# powerbrain2.net
KiCad netlist of a schematic drawn in EAGLE
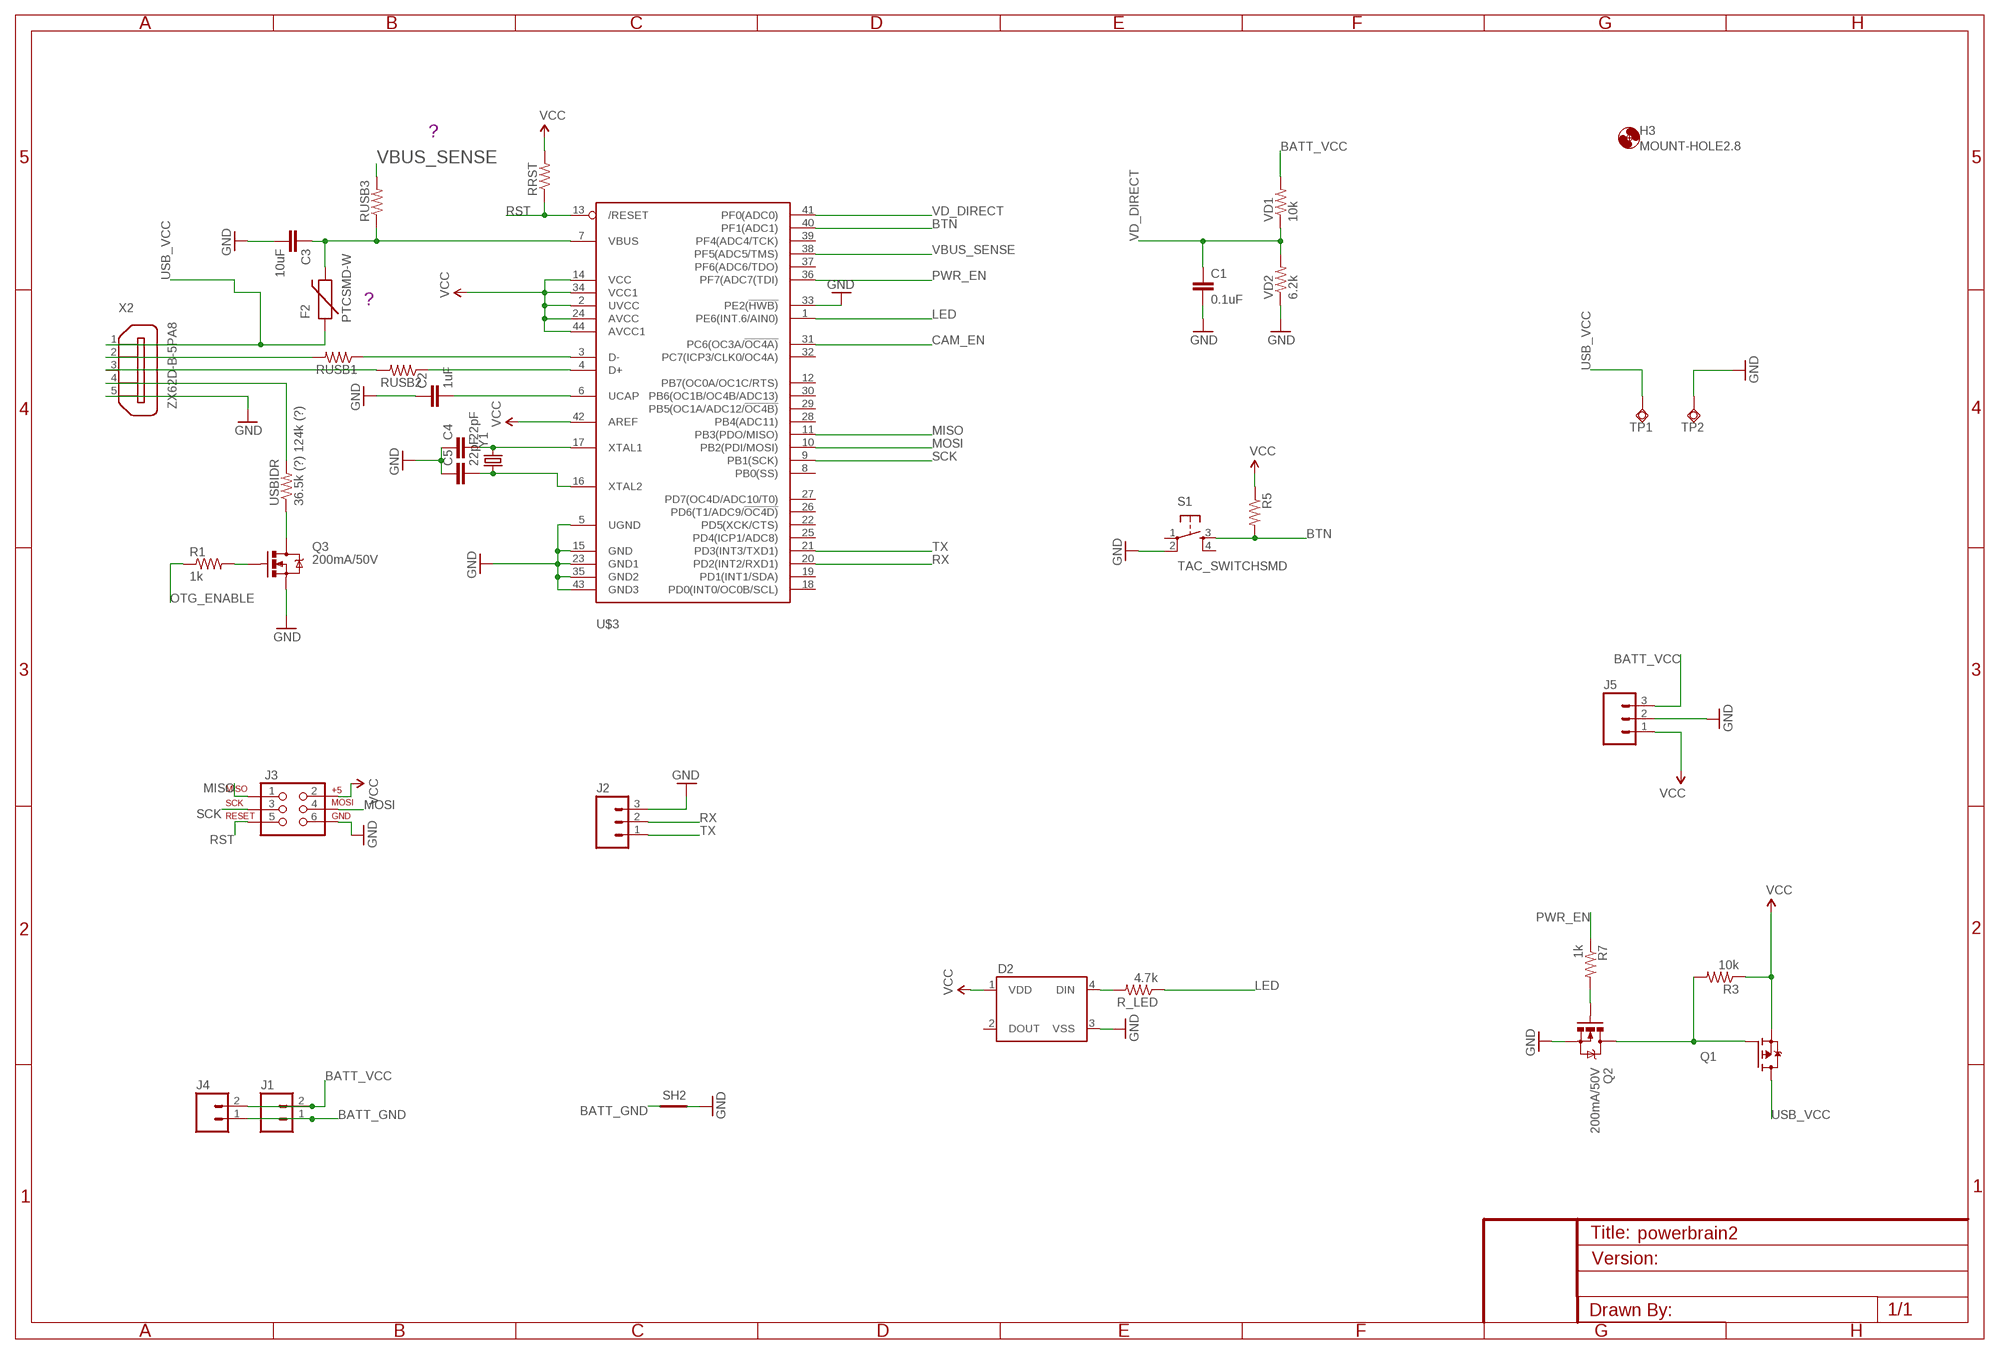
[diagram p0: schematic, sheet 1]

(export (version "E")
  (design (tool "Eeschema 10.0.6"))
  (components
    (comp (ref "C1")
      (value "0.1uF")
      (footprint "eagle-import:1206")
      (libsource (lib "eagle-import") (part "SparkFun-Passives_CAP1206"))
    )
    (comp (ref "C2")
      (value "1uF")
      (footprint "eagle-import:1206")
      (libsource (lib "eagle-import") (part "CAP1206"))
    )
    (comp (ref "C3")
      (value "10uF")
      (footprint "eagle-import:1206")
      (libsource (lib "eagle-import") (part "SparkFun-Passives_CAP1206"))
    )
    (comp (ref "C4")
      (value "22pF")
      (footprint "eagle-import:1206")
      (libsource (lib "eagle-import") (part "SparkFun-Passives_CAP1206"))
    )
    (comp (ref "C5")
      (value "22pF")
      (footprint "eagle-import:1206")
      (libsource (lib "eagle-import") (part "SparkFun-Passives_CAP1206"))
    )
    (comp (ref "D2")
      (value "WS2812B")
      (footprint "eagle-import:WS2812B")
      (libsource (lib "eagle-import") (part "WS2812B"))
    )
    (comp (ref "F2")
      (value "PTCSMD-W")
      (footprint "eagle-import:PTC-1206-WIDE")
      (libsource (lib "eagle-import") (part "PTCSMD-W"))
    )
    (comp (ref "H3")
      (value "MOUNT-HOLE2.8")
      (footprint "eagle-import:2,8")
      (libsource (lib "eagle-import") (part "MOUNT-HOLE2.8"))
    )
    (comp (ref "J1")
      (value "M02LOCK")
      (footprint "eagle-import:1X02_LOCK")
      (libsource (lib "eagle-import") (part "M02LOCK"))
    )
    (comp (ref "J2")
      (value "M03PTH")
      (footprint "eagle-import:1X03")
      (libsource (lib "eagle-import") (part "M03PTH"))
    )
    (comp (ref "J3")
      (value "AVR_SPI_PRG_6PTH")
      (footprint "eagle-import:2X3")
      (libsource (lib "eagle-import") (part "AVR_SPI_PRG_6PTH"))
    )
    (comp (ref "J4")
      (value "M02LOCK")
      (footprint "eagle-import:1X02_LOCK")
      (libsource (lib "eagle-import") (part "M02LOCK"))
    )
    (comp (ref "J5")
      (value "M03LOCK")
      (footprint "eagle-import:1X03_LOCK")
      (libsource (lib "eagle-import") (part "M03LOCK"))
    )
    (comp (ref "Q1")
      (value "FDD4141TO252")
      (footprint "eagle-import:TO252")
      (libsource (lib "eagle-import") (part "FDD4141TO252"))
    )
    (comp (ref "Q2")
      (value "200mA/50V")
      (footprint "eagle-import:SOT23-3")
      (libsource (lib "eagle-import") (part "MOSFET-NCHANNELBSS138"))
    )
    (comp (ref "Q3")
      (value "200mA/50V")
      (footprint "eagle-import:SOT23-3")
      (libsource (lib "eagle-import") (part "MOSFET-NCHANNELBSS138"))
    )
    (comp (ref "R1")
      (value "1k")
      (footprint "eagle-import:1206")
      (libsource (lib "eagle-import") (part "SparkFun-Resistors_RESISTOR1206"))
    )
    (comp (ref "R3")
      (value "10k")
      (footprint "eagle-import:1206")
      (libsource (lib "eagle-import") (part "SparkFun-Resistors_RESISTOR1206"))
    )
    (comp (ref "R5")
      (value "RESISTOR1206")
      (footprint "eagle-import:1206")
      (libsource (lib "eagle-import") (part "RESISTOR1206"))
    )
    (comp (ref "R7")
      (value "1k")
      (footprint "eagle-import:1206")
      (libsource (lib "eagle-import") (part "SparkFun-Resistors_RESISTOR1206"))
    )
    (comp (ref "RRST")
      (value "RESISTOR1206")
      (footprint "eagle-import:1206")
      (libsource (lib "eagle-import") (part "RESISTOR1206"))
    )
    (comp (ref "RUSB1")
      (value "RESISTOR1206")
      (footprint "eagle-import:1206")
      (libsource (lib "eagle-import") (part "RESISTOR1206"))
    )
    (comp (ref "RUSB2")
      (value "RESISTOR1206")
      (footprint "eagle-import:1206")
      (libsource (lib "eagle-import") (part "RESISTOR1206"))
    )
    (comp (ref "RUSB3")
      (value "RESISTOR1206")
      (footprint "eagle-import:1206")
      (libsource (lib "eagle-import") (part "RESISTOR1206"))
    )
    (comp (ref "R_LED")
      (value "4.7k")
      (footprint "eagle-import:1206")
      (libsource (lib "eagle-import") (part "SparkFun-Resistors_RESISTOR1206"))
    )
    (comp (ref "S1")
      (value "TAC_SWITCHSMD")
      (footprint "eagle-import:TACTILE-PTH")
      (libsource (lib "eagle-import") (part "TAC_SWITCHPTH"))
    )
    (comp (ref "SH2")
      (value "SHORT-HT5")
      (footprint "eagle-import:SHORT_TOP-50")
      (libsource (lib "eagle-import") (part "SHORT-HT5"))
    )
    (comp (ref "TP1")
      (value "TPSQTP20R")
      (footprint "eagle-import:TP20R")
      (libsource (lib "eagle-import") (part "TPSQTP20R"))
    )
    (comp (ref "TP2")
      (value "TPSQTP20R")
      (footprint "eagle-import:TP20R")
      (libsource (lib "eagle-import") (part "TPSQTP20R"))
    )
    (comp (ref "U$3")
      (value "ATMEGA32U4-AU")
      (footprint "eagle-import:TQFP44")
      (libsource (lib "eagle-import") (part "ATMEGA32U4-AU"))
    )
    (comp (ref "USBIDR")
      (value "36.5k (?) 124k (?)")
      (footprint "eagle-import:1206")
      (libsource (lib "eagle-import") (part "RESISTOR1206"))
    )
    (comp (ref "VD1")
      (value "10k")
      (footprint "eagle-import:1206")
      (libsource (lib "eagle-import") (part "RESISTOR1206"))
    )
    (comp (ref "VD2")
      (value "6.2k")
      (footprint "eagle-import:1206")
      (libsource (lib "eagle-import") (part "RESISTOR1206"))
    )
    (comp (ref "X2")
      (value "ZX62D-B-5PA8")
      (footprint "eagle-import:ZX62D-B-5PA8")
      (fields (field (name "MF") "Hirose"))
      (libsource (lib "eagle-import") (part "ZX62D-B-5PA8"))
    )
    (comp (ref "Y1")
      (value "CRYSTALCRYSTAL-SMD-5X3-16MHZ")
      (footprint "eagle-import:CRYSTAL-SMD-5X3")
      (libsource (lib "eagle-import") (part "CRYSTALCRYSTAL-SMD-5X3-16MHZ"))
    )
  )
  (nets
    (net (code "1") (name "/BATT_GND") (class "Default")
      (node (ref "J1") (pin "1") (pinfunction "1_1") (pintype "passive"))
      (node (ref "J4") (pin "1") (pinfunction "1_1") (pintype "passive"))
      (node (ref "SH2") (pin "1") (pinfunction "P$1_1") (pintype "bidirectional"))
    )
    (net (code "2") (name "/BATT_VCC") (class "Default")
      (node (ref "J1") (pin "2") (pinfunction "2_2") (pintype "passive"))
      (node (ref "J4") (pin "2") (pinfunction "2_2") (pintype "passive"))
      (node (ref "J5") (pin "3") (pinfunction "3_3") (pintype "passive"))
      (node (ref "VD1") (pin "2") (pinfunction "2_2") (pintype "passive"))
    )
    (net (code "3") (name "/BTN") (class "Default")
      (node (ref "R5") (pin "2") (pinfunction "2_2") (pintype "passive"))
      (node (ref "S1") (pin "3") (pinfunction "3_3") (pintype "passive"))
      (node (ref "U$3") (pin "40") (pinfunction "PF1(ADC1)_40") (pintype "bidirectional"))
    )
    (net (code "4") (name "/CAM_EN") (class "Default")
      (node (ref "U$3") (pin "31") (pinfunction "PC6(OC3A/~{OC4A})_31") (pintype "bidirectional"))
    )
    (net (code "5") (name "/LED") (class "Default")
      (node (ref "R_LED") (pin "1") (pinfunction "1_1") (pintype "passive"))
      (node (ref "U$3") (pin "1") (pinfunction "PE6(INT.6/AIN0)_1") (pintype "bidirectional"))
    )
    (net (code "6") (name "/MISO") (class "Default")
      (node (ref "J3") (pin "1") (pinfunction "1_1") (pintype "passive"))
      (node (ref "U$3") (pin "11") (pinfunction "PB3(PDO/MISO)_11") (pintype "bidirectional"))
    )
    (net (code "7") (name "/MOSI") (class "Default")
      (node (ref "J3") (pin "4") (pinfunction "4_4") (pintype "passive"))
      (node (ref "U$3") (pin "10") (pinfunction "PB2(PDI/MOSI)_10") (pintype "bidirectional"))
    )
    (net (code "8") (name "/OTG_ENABLE") (class "Default")
      (node (ref "R1") (pin "1") (pinfunction "1_1") (pintype "passive"))
    )
    (net (code "9") (name "/PWR_EN") (class "Default")
      (node (ref "R7") (pin "1") (pinfunction "1_1") (pintype "passive"))
      (node (ref "U$3") (pin "36") (pinfunction "PF7(ADC7(TDI)_36") (pintype "bidirectional"))
    )
    (net (code "10") (name "/RST") (class "Default")
      (node (ref "J3") (pin "5") (pinfunction "5_5") (pintype "passive"))
      (node (ref "RRST") (pin "1") (pinfunction "1_1") (pintype "passive"))
      (node (ref "U$3") (pin "13") (pinfunction "/RESET_13") (pintype "bidirectional"))
    )
    (net (code "11") (name "/RX") (class "Default")
      (node (ref "J2") (pin "2") (pinfunction "2_2") (pintype "passive"))
      (node (ref "U$3") (pin "20") (pinfunction "PD2(INT2/RXD1)_20") (pintype "bidirectional"))
    )
    (net (code "12") (name "/SCK") (class "Default")
      (node (ref "J3") (pin "3") (pinfunction "3_3") (pintype "passive"))
      (node (ref "U$3") (pin "9") (pinfunction "PB1(SCK)_9") (pintype "bidirectional"))
    )
    (net (code "13") (name "/TX") (class "Default")
      (node (ref "J2") (pin "1") (pinfunction "1_1") (pintype "passive"))
      (node (ref "U$3") (pin "21") (pinfunction "PD3(INT3/TXD1)_21") (pintype "bidirectional"))
    )
    (net (code "14") (name "/USB_VCC") (class "Default")
      (node (ref "F2") (pin "1") (pinfunction "1_1") (pintype "bidirectional"))
      (node (ref "Q1") (pin "3") (pinfunction "D_3") (pintype "passive"))
      (node (ref "TP1") (pin "TP") (pinfunction "TP_TP") (pintype "input"))
      (node (ref "X2") (pin "1") (pinfunction "1_1") (pintype "passive"))
    )
    (net (code "15") (name "/VBUS_SENSE") (class "Default")
      (node (ref "RUSB3") (pin "2") (pinfunction "2_2") (pintype "passive"))
      (node (ref "U$3") (pin "38") (pinfunction "PF5(ADC5/TMS)_38") (pintype "bidirectional"))
    )
    (net (code "16") (name "/VD_DIRECT") (class "Default")
      (node (ref "C1") (pin "1") (pinfunction "1_1") (pintype "passive"))
      (node (ref "U$3") (pin "41") (pinfunction "PF0(ADC0)_41") (pintype "bidirectional"))
      (node (ref "VD1") (pin "1") (pinfunction "1_1") (pintype "passive"))
      (node (ref "VD2") (pin "2") (pinfunction "2_2") (pintype "passive"))
    )
    (net (code "17") (name "GND") (class "Default")
      (node (ref "C1") (pin "2") (pinfunction "2_2") (pintype "passive"))
      (node (ref "C2") (pin "1") (pinfunction "1_1") (pintype "passive"))
      (node (ref "C3") (pin "2") (pinfunction "2_2") (pintype "passive"))
      (node (ref "C4") (pin "1") (pinfunction "1_1") (pintype "passive"))
      (node (ref "C5") (pin "1") (pinfunction "1_1") (pintype "passive"))
      (node (ref "D2") (pin "3") (pinfunction "VSS_3") (pintype "power_in"))
      (node (ref "J2") (pin "3") (pinfunction "3_3") (pintype "passive"))
      (node (ref "J3") (pin "6") (pinfunction "6_6") (pintype "passive"))
      (node (ref "J5") (pin "2") (pinfunction "2_2") (pintype "passive"))
      (node (ref "Q2") (pin "2") (pinfunction "S_2") (pintype "passive"))
      (node (ref "Q3") (pin "2") (pinfunction "S_2") (pintype "passive"))
      (node (ref "S1") (pin "2") (pinfunction "2_2") (pintype "passive"))
      (node (ref "SH2") (pin "2") (pinfunction "P$2_2") (pintype "bidirectional"))
      (node (ref "TP2") (pin "TP") (pinfunction "TP_TP") (pintype "input"))
      (node (ref "U$3") (pin "15") (pinfunction "GND_15") (pintype "bidirectional"))
      (node (ref "U$3") (pin "23") (pinfunction "GND1_23") (pintype "bidirectional"))
      (node (ref "U$3") (pin "33") (pinfunction "PE2(~{HWB})_33") (pintype "bidirectional"))
      (node (ref "U$3") (pin "35") (pinfunction "GND2_35") (pintype "bidirectional"))
      (node (ref "U$3") (pin "43") (pinfunction "GND3_43") (pintype "bidirectional"))
      (node (ref "U$3") (pin "5") (pinfunction "UGND_5") (pintype "bidirectional"))
      (node (ref "VD2") (pin "1") (pinfunction "1_1") (pintype "passive"))
      (node (ref "X2") (pin "5") (pinfunction "5_5") (pintype "passive"))
    )
    (net (code "18") (name "Net-(D2-DIN)") (class "Default")
      (node (ref "D2") (pin "4") (pinfunction "DIN_4") (pintype "input"))
      (node (ref "R_LED") (pin "2") (pinfunction "2_2") (pintype "passive"))
    )
    (net (code "19") (name "Net-(Q1-G)") (class "Default")
      (node (ref "Q1") (pin "1") (pinfunction "G_1") (pintype "passive"))
      (node (ref "Q2") (pin "3") (pinfunction "D_3") (pintype "passive"))
      (node (ref "R3") (pin "2") (pinfunction "2_2") (pintype "passive"))
    )
    (net (code "20") (name "Net-(Q2-G)") (class "Default")
      (node (ref "Q2") (pin "1") (pinfunction "G_1") (pintype "passive"))
      (node (ref "R7") (pin "2") (pinfunction "2_2") (pintype "passive"))
    )
    (net (code "21") (name "Net-(Q3-D)") (class "Default")
      (node (ref "Q3") (pin "3") (pinfunction "D_3") (pintype "passive"))
      (node (ref "USBIDR") (pin "1") (pinfunction "1_1") (pintype "passive"))
    )
    (net (code "22") (name "Net-(Q3-G)") (class "Default")
      (node (ref "Q3") (pin "1") (pinfunction "G_1") (pintype "passive"))
      (node (ref "R1") (pin "2") (pinfunction "2_2") (pintype "passive"))
    )
    (net (code "23") (name "Net-(RUSB1-Pad2)") (class "Default")
      (node (ref "RUSB1") (pin "2") (pinfunction "2_2") (pintype "passive"))
      (node (ref "X2") (pin "2") (pinfunction "2_2") (pintype "passive"))
    )
    (net (code "24") (name "Net-(RUSB2-Pad2)") (class "Default")
      (node (ref "RUSB2") (pin "2") (pinfunction "2_2") (pintype "passive"))
      (node (ref "X2") (pin "3") (pinfunction "3_3") (pintype "passive"))
    )
    (net (code "25") (name "Net-(U$3-D+)") (class "Default")
      (node (ref "RUSB2") (pin "1") (pinfunction "1_1") (pintype "passive"))
      (node (ref "U$3") (pin "4") (pinfunction "D+_4") (pintype "bidirectional"))
    )
    (net (code "26") (name "Net-(U$3-D-)") (class "Default")
      (node (ref "RUSB1") (pin "1") (pinfunction "1_1") (pintype "passive"))
      (node (ref "U$3") (pin "3") (pinfunction "D-_3") (pintype "bidirectional"))
    )
    (net (code "27") (name "Net-(U$3-UCAP)") (class "Default")
      (node (ref "C2") (pin "2") (pinfunction "2_2") (pintype "passive"))
      (node (ref "U$3") (pin "6") (pinfunction "UCAP_6") (pintype "bidirectional"))
    )
    (net (code "28") (name "Net-(U$3-VBUS)") (class "Default")
      (node (ref "C3") (pin "1") (pinfunction "1_1") (pintype "passive"))
      (node (ref "F2") (pin "2") (pinfunction "2_2") (pintype "bidirectional"))
      (node (ref "RUSB3") (pin "1") (pinfunction "1_1") (pintype "passive"))
      (node (ref "U$3") (pin "7") (pinfunction "VBUS_7") (pintype "bidirectional"))
    )
    (net (code "29") (name "Net-(U$3-XTAL1)") (class "Default")
      (node (ref "C4") (pin "2") (pinfunction "2_2") (pintype "passive"))
      (node (ref "U$3") (pin "17") (pinfunction "XTAL1_17") (pintype "bidirectional"))
      (node (ref "Y1") (pin "3") (pinfunction "2_3") (pintype "passive"))
    )
    (net (code "30") (name "Net-(U$3-XTAL2)") (class "Default")
      (node (ref "C5") (pin "2") (pinfunction "2_2") (pintype "passive"))
      (node (ref "U$3") (pin "16") (pinfunction "XTAL2_16") (pintype "bidirectional"))
      (node (ref "Y1") (pin "1") (pinfunction "1_1") (pintype "passive"))
    )
    (net (code "31") (name "Net-(USBIDR-Pad2)") (class "Default")
      (node (ref "USBIDR") (pin "2") (pinfunction "2_2") (pintype "passive"))
      (node (ref "X2") (pin "4") (pinfunction "4_4") (pintype "passive"))
    )
    (net (code "32") (name "VCC") (class "Default")
      (node (ref "D2") (pin "1") (pinfunction "VDD_1") (pintype "power_in"))
      (node (ref "J3") (pin "2") (pinfunction "2_2") (pintype "passive"))
      (node (ref "J5") (pin "1") (pinfunction "1_1") (pintype "passive"))
      (node (ref "Q1") (pin "2") (pinfunction "S_2") (pintype "passive"))
      (node (ref "R3") (pin "1") (pinfunction "1_1") (pintype "passive"))
      (node (ref "R5") (pin "1") (pinfunction "1_1") (pintype "passive"))
      (node (ref "RRST") (pin "2") (pinfunction "2_2") (pintype "passive"))
      (node (ref "U$3") (pin "14") (pinfunction "VCC_14") (pintype "bidirectional"))
      (node (ref "U$3") (pin "2") (pinfunction "UVCC_2") (pintype "bidirectional"))
      (node (ref "U$3") (pin "24") (pinfunction "AVCC_24") (pintype "bidirectional"))
      (node (ref "U$3") (pin "34") (pinfunction "VCC1_34") (pintype "bidirectional"))
      (node (ref "U$3") (pin "42") (pinfunction "AREF_42") (pintype "bidirectional"))
      (node (ref "U$3") (pin "44") (pinfunction "AVCC1_44") (pintype "bidirectional"))
    )
    (net (code "33") (name "unconnected-(D2-DOUT-Pad2)") (class "Default")
      (node (ref "D2") (pin "2") (pinfunction "DOUT_2") (pintype "output"))
    )
    (net (code "34") (name "unconnected-(S1-Pad1)") (class "Default")
      (node (ref "S1") (pin "1") (pinfunction "1_1") (pintype "passive"))
    )
    (net (code "35") (name "unconnected-(S1-Pad4)") (class "Default")
      (node (ref "S1") (pin "4") (pinfunction "4_4") (pintype "passive"))
    )
    (net (code "36") (name "unconnected-(U$3-PB0(SS)-Pad8)") (class "Default")
      (node (ref "U$3") (pin "8") (pinfunction "PB0(SS)_8") (pintype "bidirectional"))
    )
    (net (code "37") (name "unconnected-(U$3-PB4(ADC11)-Pad28)") (class "Default")
      (node (ref "U$3") (pin "28") (pinfunction "PB4(ADC11)_28") (pintype "bidirectional"))
    )
    (net (code "38") (name "unconnected-(U$3-PB5(OC1A{slash}ADC12{slash}~{OC4B})-Pad29)") (class "Default")
      (node (ref "U$3") (pin "29") (pinfunction "PB5(OC1A/ADC12/~{OC4B})_29") (pintype "bidirectional"))
    )
    (net (code "39") (name "unconnected-(U$3-PB6(OC1B{slash}OC4B{slash}ADC13)-Pad30)") (class "Default")
      (node (ref "U$3") (pin "30") (pinfunction "PB6(OC1B/OC4B/ADC13)_30") (pintype "bidirectional"))
    )
    (net (code "40") (name "unconnected-(U$3-PB7(OC0A{slash}OC1C{slash}RTS)-Pad12)") (class "Default")
      (node (ref "U$3") (pin "12") (pinfunction "PB7(OC0A/OC1C/RTS)_12") (pintype "bidirectional"))
    )
    (net (code "41") (name "unconnected-(U$3-PC7(ICP3{slash}CLK0{slash}OC4A)-Pad32)") (class "Default")
      (node (ref "U$3") (pin "32") (pinfunction "PC7(ICP3/CLK0/OC4A)_32") (pintype "bidirectional"))
    )
    (net (code "42") (name "unconnected-(U$3-PD0(INT0{slash}OC0B{slash}SCL)-Pad18)") (class "Default")
      (node (ref "U$3") (pin "18") (pinfunction "PD0(INT0/OC0B/SCL)_18") (pintype "bidirectional"))
    )
    (net (code "43") (name "unconnected-(U$3-PD1(INT1{slash}SDA)-Pad19)") (class "Default")
      (node (ref "U$3") (pin "19") (pinfunction "PD1(INT1/SDA)_19") (pintype "bidirectional"))
    )
    (net (code "44") (name "unconnected-(U$3-PD4(ICP1{slash}ADC8)-Pad25)") (class "Default")
      (node (ref "U$3") (pin "25") (pinfunction "PD4(ICP1/ADC8)_25") (pintype "bidirectional"))
    )
    (net (code "45") (name "unconnected-(U$3-PD5(XCK{slash}CTS)-Pad22)") (class "Default")
      (node (ref "U$3") (pin "22") (pinfunction "PD5(XCK/CTS)_22") (pintype "bidirectional"))
    )
    (net (code "46") (name "unconnected-(U$3-PD6(T1{slash}ADC9{slash}~{OC4D})-Pad26)") (class "Default")
      (node (ref "U$3") (pin "26") (pinfunction "PD6(T1/ADC9/~{OC4D})_26") (pintype "bidirectional"))
    )
    (net (code "47") (name "unconnected-(U$3-PD7(OC4D{slash}ADC10{slash}T0)-Pad27)") (class "Default")
      (node (ref "U$3") (pin "27") (pinfunction "PD7(OC4D/ADC10/T0)_27") (pintype "bidirectional"))
    )
    (net (code "48") (name "unconnected-(U$3-PF4(ADC4{slash}TCK)-Pad39)") (class "Default")
      (node (ref "U$3") (pin "39") (pinfunction "PF4(ADC4/TCK)_39") (pintype "bidirectional"))
    )
    (net (code "49") (name "unconnected-(U$3-PF6(ADC6{slash}TDO)-Pad37)") (class "Default")
      (node (ref "U$3") (pin "37") (pinfunction "PF6(ADC6/TDO)_37") (pintype "bidirectional"))
    )
  )
)
